# bandpass_40m_v3.net
KiCad netlist of a schematic drawn in EAGLE
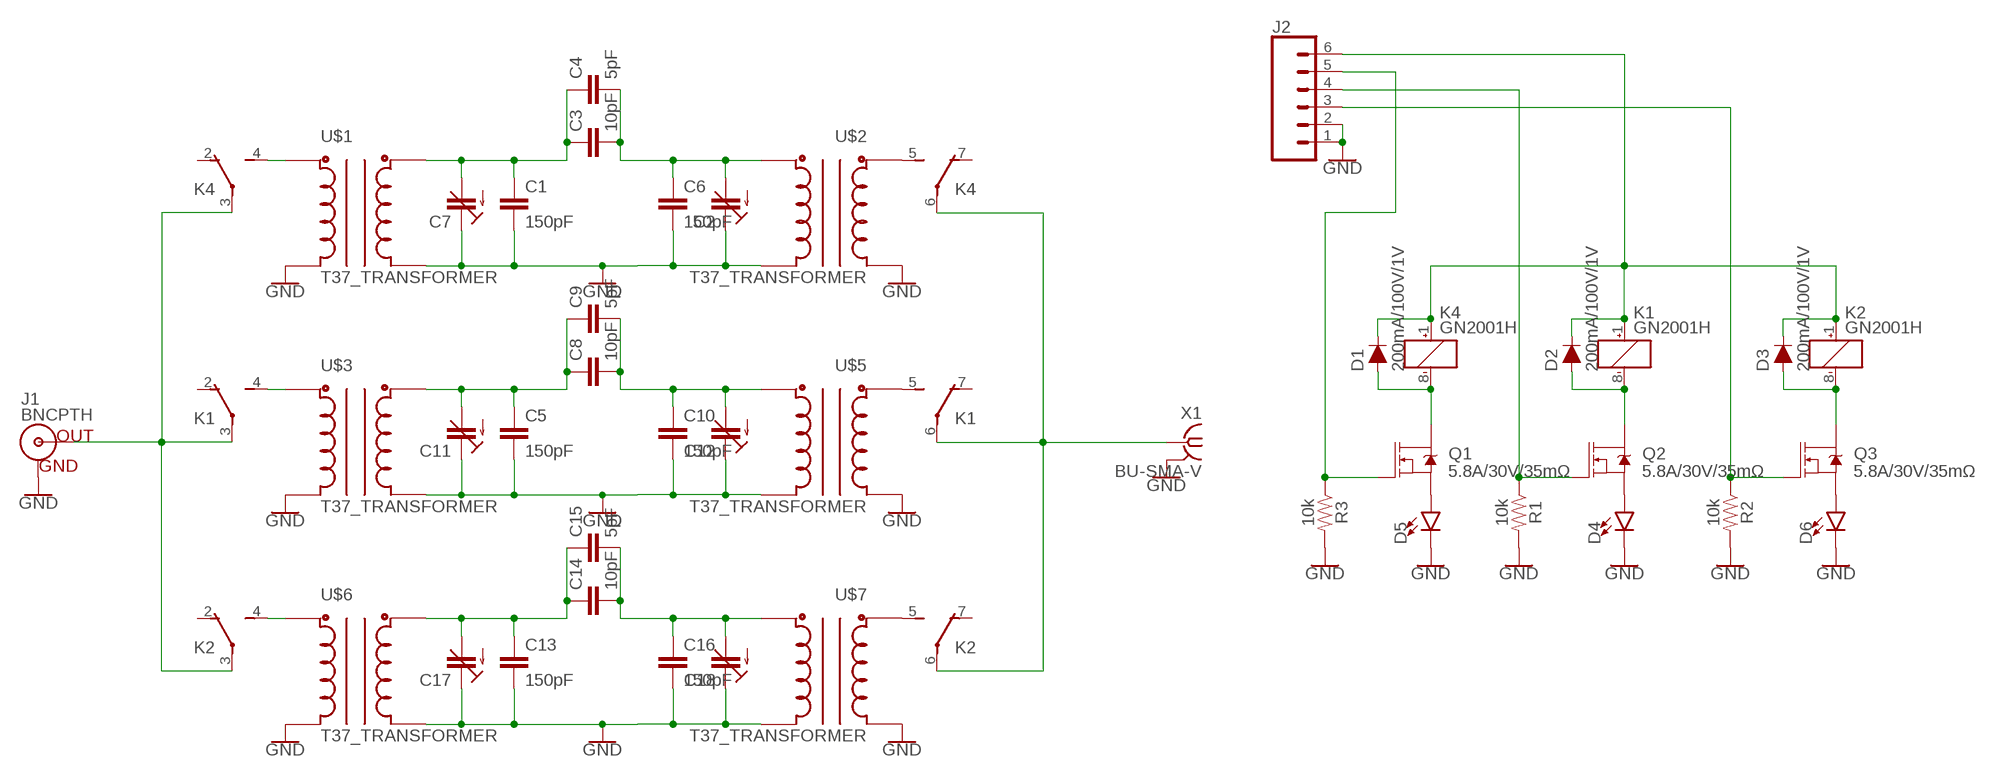
[diagram p0: schematic, sheet 1]

(export (version "E")
  (design (tool "Eeschema 10.0.6"))
  (components
    (comp (ref "C1")
      (value "150pF")
      (footprint "eagle-import:C5B3.5")
      (libsource (lib "eagle-import") (part "C5/3.5"))
    )
    (comp (ref "C2")
      (value "C-TRIMMTZ03")
      (footprint "eagle-import:CTRIMTZ03")
      (libsource (lib "eagle-import") (part "C-TRIMMTZ03"))
    )
    (comp (ref "C3")
      (value "10pF")
      (footprint "eagle-import:C5B3.5")
      (libsource (lib "eagle-import") (part "C5/3.5"))
    )
    (comp (ref "C4")
      (value "5pF")
      (footprint "eagle-import:C5B3.5")
      (libsource (lib "eagle-import") (part "C5/3.5"))
    )
    (comp (ref "C5")
      (value "150pF")
      (footprint "eagle-import:C5B3.5")
      (libsource (lib "eagle-import") (part "C5/3.5"))
    )
    (comp (ref "C6")
      (value "150pF")
      (footprint "eagle-import:C5B3.5")
      (libsource (lib "eagle-import") (part "C5/3.5"))
    )
    (comp (ref "C7")
      (value "C-TRIMMTZ03")
      (footprint "eagle-import:CTRIMTZ03")
      (libsource (lib "eagle-import") (part "C-TRIMMTZ03"))
    )
    (comp (ref "C8")
      (value "10pF")
      (footprint "eagle-import:C5B3.5")
      (libsource (lib "eagle-import") (part "C5/3.5"))
    )
    (comp (ref "C9")
      (value "5pF")
      (footprint "eagle-import:C5B3.5")
      (libsource (lib "eagle-import") (part "C5/3.5"))
    )
    (comp (ref "C10")
      (value "150pF")
      (footprint "eagle-import:C5B3.5")
      (libsource (lib "eagle-import") (part "C5/3.5"))
    )
    (comp (ref "C11")
      (value "C-TRIMMTZ03")
      (footprint "eagle-import:CTRIMTZ03")
      (libsource (lib "eagle-import") (part "C-TRIMMTZ03"))
    )
    (comp (ref "C12")
      (value "C-TRIMMTZ03")
      (footprint "eagle-import:CTRIMTZ03")
      (libsource (lib "eagle-import") (part "C-TRIMMTZ03"))
    )
    (comp (ref "C13")
      (value "150pF")
      (footprint "eagle-import:C5B3.5")
      (libsource (lib "eagle-import") (part "C5/3.5"))
    )
    (comp (ref "C14")
      (value "10pF")
      (footprint "eagle-import:C5B3.5")
      (libsource (lib "eagle-import") (part "C5/3.5"))
    )
    (comp (ref "C15")
      (value "5pF")
      (footprint "eagle-import:C5B3.5")
      (libsource (lib "eagle-import") (part "C5/3.5"))
    )
    (comp (ref "C16")
      (value "150pF")
      (footprint "eagle-import:C5B3.5")
      (libsource (lib "eagle-import") (part "C5/3.5"))
    )
    (comp (ref "C17")
      (value "C-TRIMMTZ03")
      (footprint "eagle-import:CTRIMTZ03")
      (libsource (lib "eagle-import") (part "C-TRIMMTZ03"))
    )
    (comp (ref "C18")
      (value "C-TRIMMTZ03")
      (footprint "eagle-import:CTRIMTZ03")
      (libsource (lib "eagle-import") (part "C-TRIMMTZ03"))
    )
    (comp (ref "D1")
      (value "200mA/100V/1V")
      (footprint "eagle-import:DIODE-1N4148")
      (libsource (lib "eagle-import") (part "DIODE-1N4148"))
    )
    (comp (ref "D2")
      (value "200mA/100V/1V")
      (footprint "eagle-import:DIODE-1N4148")
      (libsource (lib "eagle-import") (part "DIODE-1N4148"))
    )
    (comp (ref "D3")
      (value "200mA/100V/1V")
      (footprint "eagle-import:DIODE-1N4148")
      (libsource (lib "eagle-import") (part "DIODE-1N4148"))
    )
    (comp (ref "D4")
      (value "LED5MM")
      (footprint "eagle-import:LED_5MM")
      (libsource (lib "eagle-import") (part "LED5MM"))
    )
    (comp (ref "D5")
      (value "LED5MM")
      (footprint "eagle-import:LED_5MM")
      (libsource (lib "eagle-import") (part "LED5MM"))
    )
    (comp (ref "D6")
      (value "LED5MM")
      (footprint "eagle-import:LED_5MM")
      (libsource (lib "eagle-import") (part "LED5MM"))
    )
    (comp (ref "J1")
      (value "BNCPTH")
      (footprint "eagle-import:BNC")
      (libsource (lib "eagle-import") (part "BNCPTH"))
    )
    (comp (ref "J2")
      (value "CONN_06LONGPADS")
      (footprint "eagle-import:1X06_LONGPADS")
      (libsource (lib "eagle-import") (part "CONN_06LONGPADS"))
    )
    (comp (ref "K1")
      (value "GN2001H")
      (footprint "eagle-import:GN")
      (libsource (lib "eagle-import") (part "GN?2001H"))
    )
    (comp (ref "K2")
      (value "GN2001H")
      (footprint "eagle-import:GN")
      (libsource (lib "eagle-import") (part "GN?2001H"))
    )
    (comp (ref "K4")
      (value "GN2001H")
      (footprint "eagle-import:GN")
      (libsource (lib "eagle-import") (part "GN?2001H"))
    )
    (comp (ref "Q1")
      (value "5.8A/30V/35mΩ")
      (footprint "eagle-import:SOT23-3")
      (libsource (lib "eagle-import") (part "MOSFET-NCH-AO3404A"))
    )
    (comp (ref "Q2")
      (value "5.8A/30V/35mΩ")
      (footprint "eagle-import:SOT23-3")
      (libsource (lib "eagle-import") (part "MOSFET-NCH-AO3404A"))
    )
    (comp (ref "Q3")
      (value "5.8A/30V/35mΩ")
      (footprint "eagle-import:SOT23-3")
      (libsource (lib "eagle-import") (part "MOSFET-NCH-AO3404A"))
    )
    (comp (ref "R1")
      (value "10k")
      (footprint "eagle-import:AXIAL-0.3")
      (libsource (lib "eagle-import") (part "1KOHM-HORIZ-1/4W-1%"))
    )
    (comp (ref "R2")
      (value "10k")
      (footprint "eagle-import:AXIAL-0.3")
      (libsource (lib "eagle-import") (part "1KOHM-HORIZ-1/4W-1%"))
    )
    (comp (ref "R3")
      (value "10k")
      (footprint "eagle-import:AXIAL-0.3")
      (libsource (lib "eagle-import") (part "1KOHM-HORIZ-1/4W-1%"))
    )
    (comp (ref "U$1")
      (value "T37_TRANSFORMER")
      (footprint "eagle-import:T37_TRANSFORMER")
      (libsource (lib "eagle-import") (part "T37_TRANSFORMER"))
    )
    (comp (ref "U$2")
      (value "T37_TRANSFORMER")
      (footprint "eagle-import:T37_TRANSFORMER")
      (libsource (lib "eagle-import") (part "T37_TRANSFORMER"))
    )
    (comp (ref "U$3")
      (value "T37_TRANSFORMER")
      (footprint "eagle-import:T37_TRANSFORMER")
      (libsource (lib "eagle-import") (part "T37_TRANSFORMER"))
    )
    (comp (ref "U$5")
      (value "T37_TRANSFORMER")
      (footprint "eagle-import:T37_TRANSFORMER")
      (libsource (lib "eagle-import") (part "T37_TRANSFORMER"))
    )
    (comp (ref "U$6")
      (value "T37_TRANSFORMER")
      (footprint "eagle-import:T37_TRANSFORMER")
      (libsource (lib "eagle-import") (part "T37_TRANSFORMER"))
    )
    (comp (ref "U$7")
      (value "T37_TRANSFORMER")
      (footprint "eagle-import:T37_TRANSFORMER")
      (libsource (lib "eagle-import") (part "T37_TRANSFORMER"))
    )
    (comp (ref "X1")
      (value "BU-SMA-V")
      (footprint "eagle-import:BU-SMA-V")
      (libsource (lib "eagle-import") (part "BU-SMA-V"))
    )
  )
  (nets
    (net (code "1") (name "GND") (class "Default")
      (node (ref "C1") (pin "2") (pinfunction "2_2") (pintype "passive"))
      (node (ref "C10") (pin "2") (pinfunction "2_2") (pintype "passive"))
      (node (ref "C11") (pin "1") (pinfunction "E_1") (pintype "passive"))
      (node (ref "C12") (pin "1") (pinfunction "E_1") (pintype "passive"))
      (node (ref "C13") (pin "2") (pinfunction "2_2") (pintype "passive"))
      (node (ref "C16") (pin "2") (pinfunction "2_2") (pintype "passive"))
      (node (ref "C17") (pin "1") (pinfunction "E_1") (pintype "passive"))
      (node (ref "C18") (pin "1") (pinfunction "E_1") (pintype "passive"))
      (node (ref "C2") (pin "1") (pinfunction "E_1") (pintype "passive"))
      (node (ref "C5") (pin "2") (pinfunction "2_2") (pintype "passive"))
      (node (ref "C6") (pin "2") (pinfunction "2_2") (pintype "passive"))
      (node (ref "C7") (pin "1") (pinfunction "E_1") (pintype "passive"))
      (node (ref "D4") (pin "K") (pinfunction "C_K") (pintype "passive"))
      (node (ref "D5") (pin "K") (pinfunction "C_K") (pintype "passive"))
      (node (ref "D6") (pin "K") (pinfunction "C_K") (pintype "passive"))
      (node (ref "J1") (pin "GND") (pinfunction "GND_GND") (pintype "bidirectional"))
      (node (ref "J2") (pin "1") (pinfunction "1_1") (pintype "passive"))
      (node (ref "J2") (pin "2") (pinfunction "2_2") (pintype "passive"))
      (node (ref "R1") (pin "P$2") (pinfunction "2_P$2") (pintype "passive"))
      (node (ref "R2") (pin "P$2") (pinfunction "2_P$2") (pintype "passive"))
      (node (ref "R3") (pin "P$2") (pinfunction "2_P$2") (pintype "passive"))
      (node (ref "U$1") (pin "C1A") (pinfunction "C1A_C1A") (pintype "bidirectional"))
      (node (ref "U$1") (pin "C2A") (pinfunction "C2A_C2A") (pintype "bidirectional"))
      (node (ref "U$2") (pin "C1A") (pinfunction "C1A_C1A") (pintype "bidirectional"))
      (node (ref "U$2") (pin "C2A") (pinfunction "C2A_C2A") (pintype "bidirectional"))
      (node (ref "U$3") (pin "C1A") (pinfunction "C1A_C1A") (pintype "bidirectional"))
      (node (ref "U$3") (pin "C2A") (pinfunction "C2A_C2A") (pintype "bidirectional"))
      (node (ref "U$5") (pin "C1A") (pinfunction "C1A_C1A") (pintype "bidirectional"))
      (node (ref "U$5") (pin "C2A") (pinfunction "C2A_C2A") (pintype "bidirectional"))
      (node (ref "U$6") (pin "C1A") (pinfunction "C1A_C1A") (pintype "bidirectional"))
      (node (ref "U$6") (pin "C2A") (pinfunction "C2A_C2A") (pintype "bidirectional"))
      (node (ref "U$7") (pin "C1A") (pinfunction "C1A_C1A") (pintype "bidirectional"))
      (node (ref "U$7") (pin "C2A") (pinfunction "C2A_C2A") (pintype "bidirectional"))
      (node (ref "X1") (pin "2") (pinfunction "2_2") (pintype "passive"))
      (node (ref "X1") (pin "3") (pinfunction "2_3") (pintype "passive"))
      (node (ref "X1") (pin "4") (pinfunction "2_4") (pintype "passive"))
      (node (ref "X1") (pin "5") (pinfunction "2_5") (pintype "passive"))
    )
    (net (code "2") (name "Net-(C2-A)") (class "Default")
      (node (ref "C2") (pin "2") (pinfunction "A_2") (pintype "passive"))
      (node (ref "C3") (pin "2") (pinfunction "2_2") (pintype "passive"))
      (node (ref "C4") (pin "2") (pinfunction "2_2") (pintype "passive"))
      (node (ref "C6") (pin "1") (pinfunction "1_1") (pintype "passive"))
      (node (ref "U$2") (pin "C2B") (pinfunction "C2B_C2B") (pintype "bidirectional"))
    )
    (net (code "3") (name "Net-(C7-A)") (class "Default")
      (node (ref "C1") (pin "1") (pinfunction "1_1") (pintype "passive"))
      (node (ref "C3") (pin "1") (pinfunction "1_1") (pintype "passive"))
      (node (ref "C4") (pin "1") (pinfunction "1_1") (pintype "passive"))
      (node (ref "C7") (pin "2") (pinfunction "A_2") (pintype "passive"))
      (node (ref "U$1") (pin "C2B") (pinfunction "C2B_C2B") (pintype "bidirectional"))
    )
    (net (code "4") (name "Net-(C11-A)") (class "Default")
      (node (ref "C11") (pin "2") (pinfunction "A_2") (pintype "passive"))
      (node (ref "C5") (pin "1") (pinfunction "1_1") (pintype "passive"))
      (node (ref "C8") (pin "1") (pinfunction "1_1") (pintype "passive"))
      (node (ref "C9") (pin "1") (pinfunction "1_1") (pintype "passive"))
      (node (ref "U$3") (pin "C2B") (pinfunction "C2B_C2B") (pintype "bidirectional"))
    )
    (net (code "5") (name "Net-(C12-A)") (class "Default")
      (node (ref "C10") (pin "1") (pinfunction "1_1") (pintype "passive"))
      (node (ref "C12") (pin "2") (pinfunction "A_2") (pintype "passive"))
      (node (ref "C8") (pin "2") (pinfunction "2_2") (pintype "passive"))
      (node (ref "C9") (pin "2") (pinfunction "2_2") (pintype "passive"))
      (node (ref "U$5") (pin "C2B") (pinfunction "C2B_C2B") (pintype "bidirectional"))
    )
    (net (code "6") (name "Net-(C17-A)") (class "Default")
      (node (ref "C13") (pin "1") (pinfunction "1_1") (pintype "passive"))
      (node (ref "C14") (pin "1") (pinfunction "1_1") (pintype "passive"))
      (node (ref "C15") (pin "1") (pinfunction "1_1") (pintype "passive"))
      (node (ref "C17") (pin "2") (pinfunction "A_2") (pintype "passive"))
      (node (ref "U$6") (pin "C2B") (pinfunction "C2B_C2B") (pintype "bidirectional"))
    )
    (net (code "7") (name "Net-(C18-A)") (class "Default")
      (node (ref "C14") (pin "2") (pinfunction "2_2") (pintype "passive"))
      (node (ref "C15") (pin "2") (pinfunction "2_2") (pintype "passive"))
      (node (ref "C16") (pin "1") (pinfunction "1_1") (pintype "passive"))
      (node (ref "C18") (pin "2") (pinfunction "A_2") (pintype "passive"))
      (node (ref "U$7") (pin "C2B") (pinfunction "C2B_C2B") (pintype "bidirectional"))
    )
    (net (code "8") (name "Net-(J1-OUT)") (class "Default")
      (node (ref "J1") (pin "S") (pinfunction "OUT_S") (pintype "bidirectional"))
      (node (ref "K1") (pin "3") (pinfunction "P_3") (pintype "passive"))
      (node (ref "K2") (pin "3") (pinfunction "P_3") (pintype "passive"))
      (node (ref "K4") (pin "3") (pinfunction "P_3") (pintype "passive"))
    )
    (net (code "9") (name "Net-(K1A-+)") (class "Default")
      (node (ref "D1") (pin "C") (pinfunction "C_C") (pintype "passive"))
      (node (ref "D2") (pin "C") (pinfunction "C_C") (pintype "passive"))
      (node (ref "D3") (pin "C") (pinfunction "C_C") (pintype "passive"))
      (node (ref "J2") (pin "6") (pinfunction "6_6") (pintype "passive"))
      (node (ref "K1") (pin "1") (pinfunction "+_1") (pintype "passive"))
      (node (ref "K2") (pin "1") (pinfunction "+_1") (pintype "passive"))
      (node (ref "K4") (pin "1") (pinfunction "+_1") (pintype "passive"))
    )
    (net (code "10") (name "Net-(K1A--)") (class "Default")
      (node (ref "D2") (pin "A") (pinfunction "A_A") (pintype "passive"))
      (node (ref "K1") (pin "8") (pinfunction "-_8") (pintype "passive"))
      (node (ref "Q2") (pin "3") (pinfunction "D_3") (pintype "bidirectional"))
    )
    (net (code "11") (name "Net-(K1B-S)") (class "Default")
      (node (ref "K1") (pin "4") (pinfunction "S_4") (pintype "passive"))
      (node (ref "U$3") (pin "C1B") (pinfunction "C1B_C1B") (pintype "bidirectional"))
    )
    (net (code "12") (name "Net-(K1C-P)") (class "Default")
      (node (ref "K1") (pin "6") (pinfunction "P_6") (pintype "passive"))
      (node (ref "K2") (pin "6") (pinfunction "P_6") (pintype "passive"))
      (node (ref "K4") (pin "6") (pinfunction "P_6") (pintype "passive"))
      (node (ref "X1") (pin "1") (pinfunction "1_1") (pintype "passive"))
    )
    (net (code "13") (name "Net-(K1C-S)") (class "Default")
      (node (ref "K1") (pin "5") (pinfunction "S_5") (pintype "passive"))
      (node (ref "U$5") (pin "C1B") (pinfunction "C1B_C1B") (pintype "bidirectional"))
    )
    (net (code "14") (name "Net-(K2A--)") (class "Default")
      (node (ref "D3") (pin "A") (pinfunction "A_A") (pintype "passive"))
      (node (ref "K2") (pin "8") (pinfunction "-_8") (pintype "passive"))
      (node (ref "Q3") (pin "3") (pinfunction "D_3") (pintype "bidirectional"))
    )
    (net (code "15") (name "Net-(K2B-S)") (class "Default")
      (node (ref "K2") (pin "4") (pinfunction "S_4") (pintype "passive"))
      (node (ref "U$6") (pin "C1B") (pinfunction "C1B_C1B") (pintype "bidirectional"))
    )
    (net (code "16") (name "Net-(K2C-S)") (class "Default")
      (node (ref "K2") (pin "5") (pinfunction "S_5") (pintype "passive"))
      (node (ref "U$7") (pin "C1B") (pinfunction "C1B_C1B") (pintype "bidirectional"))
    )
    (net (code "17") (name "Net-(K4A--)") (class "Default")
      (node (ref "D1") (pin "A") (pinfunction "A_A") (pintype "passive"))
      (node (ref "K4") (pin "8") (pinfunction "-_8") (pintype "passive"))
      (node (ref "Q1") (pin "3") (pinfunction "D_3") (pintype "bidirectional"))
    )
    (net (code "18") (name "Net-(K4B-S)") (class "Default")
      (node (ref "K4") (pin "4") (pinfunction "S_4") (pintype "passive"))
      (node (ref "U$1") (pin "C1B") (pinfunction "C1B_C1B") (pintype "bidirectional"))
    )
    (net (code "19") (name "Net-(K4C-S)") (class "Default")
      (node (ref "K4") (pin "5") (pinfunction "S_5") (pintype "passive"))
      (node (ref "U$2") (pin "C1B") (pinfunction "C1B_C1B") (pintype "bidirectional"))
    )
    (net (code "20") (name "Net-(Q1-G)") (class "Default")
      (node (ref "J2") (pin "5") (pinfunction "5_5") (pintype "passive"))
      (node (ref "Q1") (pin "1") (pinfunction "G_1") (pintype "bidirectional"))
      (node (ref "R3") (pin "P$1") (pinfunction "1_P$1") (pintype "passive"))
    )
    (net (code "21") (name "Net-(Q1-S)") (class "Default")
      (node (ref "D5") (pin "A") (pinfunction "A_A") (pintype "passive"))
      (node (ref "Q1") (pin "2") (pinfunction "S_2") (pintype "bidirectional"))
    )
    (net (code "22") (name "Net-(Q2-G)") (class "Default")
      (node (ref "J2") (pin "4") (pinfunction "4_4") (pintype "passive"))
      (node (ref "Q2") (pin "1") (pinfunction "G_1") (pintype "bidirectional"))
      (node (ref "R1") (pin "P$1") (pinfunction "1_P$1") (pintype "passive"))
    )
    (net (code "23") (name "Net-(Q2-S)") (class "Default")
      (node (ref "D4") (pin "A") (pinfunction "A_A") (pintype "passive"))
      (node (ref "Q2") (pin "2") (pinfunction "S_2") (pintype "bidirectional"))
    )
    (net (code "24") (name "Net-(Q3-G)") (class "Default")
      (node (ref "J2") (pin "3") (pinfunction "3_3") (pintype "passive"))
      (node (ref "Q3") (pin "1") (pinfunction "G_1") (pintype "bidirectional"))
      (node (ref "R2") (pin "P$1") (pinfunction "1_P$1") (pintype "passive"))
    )
    (net (code "25") (name "Net-(Q3-S)") (class "Default")
      (node (ref "D6") (pin "A") (pinfunction "A_A") (pintype "passive"))
      (node (ref "Q3") (pin "2") (pinfunction "S_2") (pintype "bidirectional"))
    )
    (net (code "26") (name "unconnected-(K1B-O-Pad2)") (class "Default")
      (node (ref "K1") (pin "2") (pinfunction "O_2") (pintype "passive"))
    )
    (net (code "27") (name "unconnected-(K1C-O-Pad7)") (class "Default")
      (node (ref "K1") (pin "7") (pinfunction "O_7") (pintype "passive"))
    )
    (net (code "28") (name "unconnected-(K2B-O-Pad2)") (class "Default")
      (node (ref "K2") (pin "2") (pinfunction "O_2") (pintype "passive"))
    )
    (net (code "29") (name "unconnected-(K2C-O-Pad7)") (class "Default")
      (node (ref "K2") (pin "7") (pinfunction "O_7") (pintype "passive"))
    )
    (net (code "30") (name "unconnected-(K4B-O-Pad2)") (class "Default")
      (node (ref "K4") (pin "2") (pinfunction "O_2") (pintype "passive"))
    )
    (net (code "31") (name "unconnected-(K4C-O-Pad7)") (class "Default")
      (node (ref "K4") (pin "7") (pinfunction "O_7") (pintype "passive"))
    )
  )
)
